# Laser_Driver_LM311.net
KiCad netlist of a schematic drawn in EAGLE
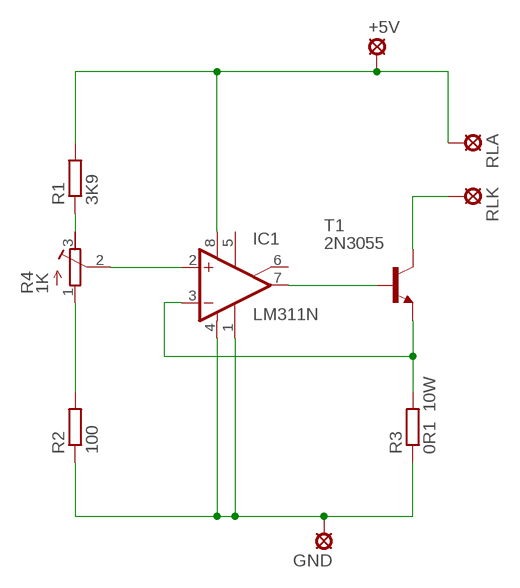
[diagram p0: schematic, sheet 1]

(export (version "E")
  (design (tool "Eeschema 10.0.6"))
  (components
    (comp (ref "+5V")
      (value "SE14")
      (footprint "eagle-import:SE14")
      (libsource (lib "eagle-import") (part "SE14"))
    )
    (comp (ref "GND")
      (value "SE14")
      (footprint "eagle-import:SE14")
      (libsource (lib "eagle-import") (part "SE14"))
    )
    (comp (ref "IC1")
      (value "LM311N")
      (footprint "eagle-import:DIL08")
      (libsource (lib "eagle-import") (part "LM311N"))
    )
    (comp (ref "R1")
      (value "3K9")
      (footprint "eagle-import:0207_12")
      (libsource (lib "eagle-import") (part "resistor_R-EU_0207/12"))
    )
    (comp (ref "R2")
      (value "100")
      (footprint "eagle-import:0207_12")
      (libsource (lib "eagle-import") (part "resistor_R-EU_0207/12"))
    )
    (comp (ref "R3")
      (value "0R1 10W")
      (footprint "eagle-import:V235_17")
      (libsource (lib "eagle-import") (part "R-EU_V235/17"))
    )
    (comp (ref "R4")
      (value "1K")
      (footprint "eagle-import:RTRIM3339P")
      (libsource (lib "eagle-import") (part "R-TRIMM3339P"))
    )
    (comp (ref "RLA")
      (value "SE14")
      (footprint "eagle-import:SE14")
      (libsource (lib "eagle-import") (part "SE14"))
    )
    (comp (ref "RLK")
      (value "SE14")
      (footprint "eagle-import:SE14")
      (libsource (lib "eagle-import") (part "SE14"))
    )
    (comp (ref "T1")
      (value "2N3055")
      (footprint "eagle-import:TO3")
      (libsource (lib "eagle-import") (part "2N3055"))
    )
  )
  (nets
    (net (code "1") (name "Net-(IC1-+IN)") (class "Default")
      (node (ref "IC1") (pin "2") (pinfunction "+IN_2") (pintype "input"))
      (node (ref "R4") (pin "2") (pinfunction "S_2") (pintype "passive"))
    )
    (net (code "2") (name "Net-(IC1--IN)") (class "Default")
      (node (ref "IC1") (pin "3") (pinfunction "-IN_3") (pintype "input"))
      (node (ref "R3") (pin "2") (pinfunction "2_2") (pintype "passive"))
      (node (ref "T1") (pin "E") (pinfunction "E_E") (pintype "passive"))
    )
    (net (code "3") (name "Net-(IC1-GND)") (class "Default")
      (node (ref "GND") (pin "MP") (pinfunction "MP_MP") (pintype "passive"))
      (node (ref "IC1") (pin "1") (pinfunction "GND_1") (pintype "passive"))
      (node (ref "IC1") (pin "4") (pinfunction "V-_4") (pintype "power_in"))
      (node (ref "R2") (pin "1") (pinfunction "1_1") (pintype "passive"))
      (node (ref "R3") (pin "1") (pinfunction "1_1") (pintype "passive"))
    )
    (net (code "4") (name "Net-(IC1-OUT)") (class "Default")
      (node (ref "IC1") (pin "7") (pinfunction "OUT_7") (pintype "output"))
      (node (ref "T1") (pin "B") (pinfunction "B_B") (pintype "passive"))
    )
    (net (code "5") (name "Net-(IC1-V+)") (class "Default")
      (node (ref "+5V") (pin "MP") (pinfunction "MP_MP") (pintype "passive"))
      (node (ref "IC1") (pin "8") (pinfunction "V+_8") (pintype "power_in"))
      (node (ref "R1") (pin "2") (pinfunction "2_2") (pintype "passive"))
      (node (ref "RLA") (pin "MP") (pinfunction "MP_MP") (pintype "passive"))
    )
    (net (code "6") (name "Net-(R4-A)") (class "Default")
      (node (ref "R2") (pin "2") (pinfunction "2_2") (pintype "passive"))
      (node (ref "R4") (pin "1") (pinfunction "A_1") (pintype "passive"))
    )
    (net (code "7") (name "Net-(R4-E)") (class "Default")
      (node (ref "R1") (pin "1") (pinfunction "1_1") (pintype "passive"))
      (node (ref "R4") (pin "3") (pinfunction "E_3") (pintype "passive"))
    )
    (net (code "8") (name "Net-(RLK-PadMP)") (class "Default")
      (node (ref "RLK") (pin "MP") (pinfunction "MP_MP") (pintype "passive"))
      (node (ref "T1") (pin "C") (pinfunction "C_C") (pintype "passive"))
      (node (ref "T1") (pin "C/") (pinfunction "C_C/") (pintype "passive"))
    )
    (net (code "9") (name "unconnected-(IC1-ON-Pad5)") (class "Default")
      (node (ref "IC1") (pin "5") (pinfunction "ON_5") (pintype "passive"))
    )
    (net (code "10") (name "unconnected-(IC1-ON{slash}STR-Pad6)") (class "Default")
      (node (ref "IC1") (pin "6") (pinfunction "ON/STR_6") (pintype "passive"))
    )
  )
)
